# EL_Inverter.net
KiCad netlist of a schematic drawn in EAGLE
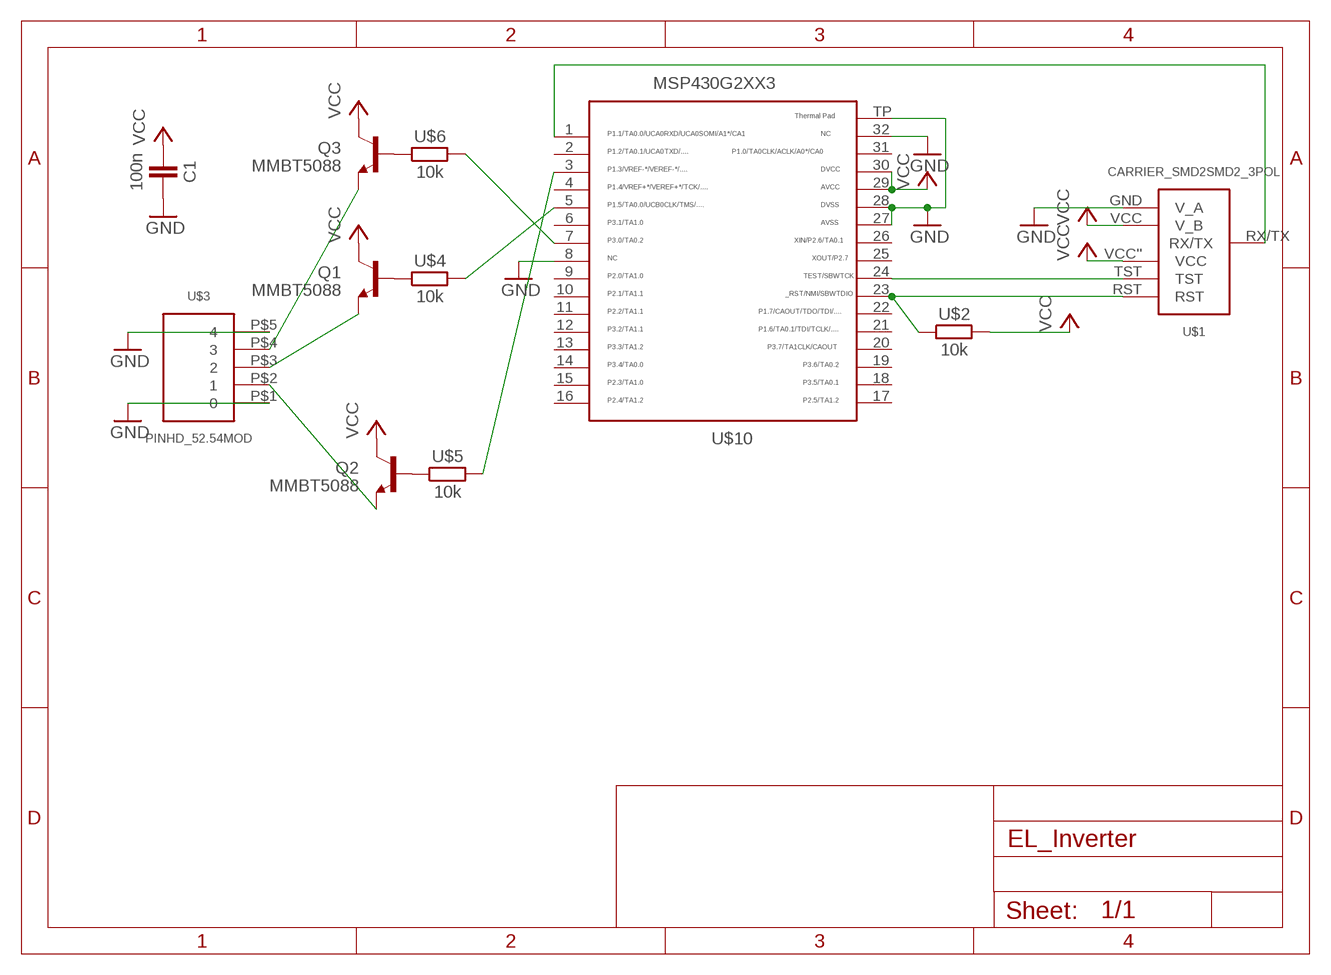
[diagram p0: schematic, sheet 1]

(export (version "E")
  (design (tool "Eeschema 10.0.6"))
  (components
    (comp (ref "C1")
      (value "100n")
      (footprint "eagle-import:603")
      (libsource (lib "eagle-import") (part "CAPACITOR"))
    )
    (comp (ref "Q1")
      (value "MMBT5088")
      (footprint "eagle-import:SOT23-3")
      (libsource (lib "eagle-import") (part "TRANSISTOR_NPNMMBT5088"))
    )
    (comp (ref "Q2")
      (value "MMBT5088")
      (footprint "eagle-import:SOT23-3")
      (libsource (lib "eagle-import") (part "TRANSISTOR_NPNMMBT5088"))
    )
    (comp (ref "Q3")
      (value "MMBT5088")
      (footprint "eagle-import:SOT23-3")
      (libsource (lib "eagle-import") (part "TRANSISTOR_NPNMMBT5088"))
    )
    (comp (ref "U$1")
      (value "CARRIER_SMD2SMD2_3POL")
      (footprint "eagle-import:CARRIER_SMD2_3POL")
      (libsource (lib "eagle-import") (part "CARRIER_SMD2SMD2_3POL"))
    )
    (comp (ref "U$2")
      (value "10k")
      (footprint "eagle-import:603")
      (libsource (lib "eagle-import") (part "RESISTOR0603"))
    )
    (comp (ref "U$3")
      (value "PINHD_52.54MOD")
      (footprint "eagle-import:PINHD_5_MOD")
      (libsource (lib "eagle-import") (part "PINHD_52.54MOD"))
    )
    (comp (ref "U$4")
      (value "10k")
      (footprint "eagle-import:603")
      (libsource (lib "eagle-import") (part "RESISTOR0603"))
    )
    (comp (ref "U$5")
      (value "10k")
      (footprint "eagle-import:603")
      (libsource (lib "eagle-import") (part "RESISTOR0603"))
    )
    (comp (ref "U$6")
      (value "10k")
      (footprint "eagle-import:603")
      (libsource (lib "eagle-import") (part "RESISTOR0603"))
    )
    (comp (ref "U$10")
      (value "MSP430G2553")
      (footprint "eagle-import:QFN32")
      (libsource (lib "eagle-import") (part "MSP430G2553"))
    )
  )
  (nets
    (net (code "1") (name "GND") (class "Default")
      (node (ref "C1") (pin "2") (pinfunction "2_2") (pintype "passive"))
      (node (ref "U$1") (pin "GND") (pinfunction "V_A_GND") (pintype "bidirectional"))
      (node (ref "U$10") (pin "27") (pinfunction "27_27") (pintype "bidirectional"))
      (node (ref "U$10") (pin "28") (pinfunction "28_28") (pintype "bidirectional"))
      (node (ref "U$10") (pin "32") (pinfunction "32_32") (pintype "bidirectional"))
      (node (ref "U$10") (pin "8") (pinfunction "8_8") (pintype "bidirectional"))
      (node (ref "U$10") (pin "TP") (pinfunction "TP_TP") (pintype "bidirectional"))
      (node (ref "U$3") (pin "P$1") (pinfunction "0_P$1") (pintype "bidirectional"))
      (node (ref "U$3") (pin "P$5") (pinfunction "4_P$5") (pintype "bidirectional"))
    )
    (net (code "2") (name "Net-(Q1-B)") (class "Default")
      (node (ref "Q1") (pin "1") (pinfunction "B_1") (pintype "passive"))
      (node (ref "U$4") (pin "1") (pinfunction "1_1") (pintype "passive"))
    )
    (net (code "3") (name "Net-(Q1-E)") (class "Default")
      (node (ref "Q1") (pin "2") (pinfunction "E_2") (pintype "passive"))
      (node (ref "U$3") (pin "P$3") (pinfunction "2_P$3") (pintype "bidirectional"))
    )
    (net (code "4") (name "Net-(Q2-B)") (class "Default")
      (node (ref "Q2") (pin "1") (pinfunction "B_1") (pintype "passive"))
      (node (ref "U$5") (pin "1") (pinfunction "1_1") (pintype "passive"))
    )
    (net (code "5") (name "Net-(Q2-E)") (class "Default")
      (node (ref "Q2") (pin "2") (pinfunction "E_2") (pintype "passive"))
      (node (ref "U$3") (pin "P$2") (pinfunction "1_P$2") (pintype "bidirectional"))
    )
    (net (code "6") (name "Net-(Q3-B)") (class "Default")
      (node (ref "Q3") (pin "1") (pinfunction "B_1") (pintype "passive"))
      (node (ref "U$6") (pin "1") (pinfunction "1_1") (pintype "passive"))
    )
    (net (code "7") (name "Net-(Q3-E)") (class "Default")
      (node (ref "Q3") (pin "2") (pinfunction "E_2") (pintype "passive"))
      (node (ref "U$3") (pin "P$4") (pinfunction "3_P$4") (pintype "bidirectional"))
    )
    (net (code "8") (name "Net-(U$1-PadRST)") (class "Default")
      (node (ref "U$1") (pin "RST") (pinfunction "RST_RST") (pintype "bidirectional"))
      (node (ref "U$10") (pin "23") (pinfunction "23_23") (pintype "bidirectional"))
      (node (ref "U$2") (pin "1") (pinfunction "1_1") (pintype "passive"))
    )
    (net (code "9") (name "Net-(U$1-PadRX{slash}TX)") (class "Default")
      (node (ref "U$1") (pin "RX/TX") (pinfunction "RX/TX_RX/TX") (pintype "bidirectional"))
      (node (ref "U$10") (pin "1") (pinfunction "1_1") (pintype "bidirectional"))
    )
    (net (code "10") (name "Net-(U$1-PadTST)") (class "Default")
      (node (ref "U$1") (pin "TST") (pinfunction "TST_TST") (pintype "bidirectional"))
      (node (ref "U$10") (pin "24") (pinfunction "24_24") (pintype "bidirectional"))
    )
    (net (code "11") (name "Net-(U$10-Pad3)") (class "Default")
      (node (ref "U$10") (pin "3") (pinfunction "3_3") (pintype "bidirectional"))
      (node (ref "U$5") (pin "2") (pinfunction "2_2") (pintype "passive"))
    )
    (net (code "12") (name "Net-(U$10-Pad5)") (class "Default")
      (node (ref "U$10") (pin "5") (pinfunction "5_5") (pintype "bidirectional"))
      (node (ref "U$4") (pin "2") (pinfunction "2_2") (pintype "passive"))
    )
    (net (code "13") (name "Net-(U$10-Pad7)") (class "Default")
      (node (ref "U$10") (pin "7") (pinfunction "7_7") (pintype "bidirectional"))
      (node (ref "U$6") (pin "2") (pinfunction "2_2") (pintype "passive"))
    )
    (net (code "14") (name "VCC") (class "Default")
      (node (ref "C1") (pin "1") (pinfunction "1_1") (pintype "passive"))
      (node (ref "Q1") (pin "3") (pinfunction "C_3") (pintype "passive"))
      (node (ref "Q2") (pin "3") (pinfunction "C_3") (pintype "passive"))
      (node (ref "Q3") (pin "3") (pinfunction "C_3") (pintype "passive"))
      (node (ref "U$1") (pin "VCC") (pinfunction "V_B_VCC") (pintype "bidirectional"))
      (node (ref "U$1") (pin "VCC''") (pinfunction "VCC_VCC''") (pintype "bidirectional"))
      (node (ref "U$10") (pin "29") (pinfunction "29_29") (pintype "bidirectional"))
      (node (ref "U$10") (pin "30") (pinfunction "30_30") (pintype "bidirectional"))
      (node (ref "U$2") (pin "2") (pinfunction "2_2") (pintype "passive"))
    )
    (net (code "15") (name "unconnected-(U$10-Pad2)") (class "Default")
      (node (ref "U$10") (pin "2") (pinfunction "2_2") (pintype "bidirectional"))
    )
    (net (code "16") (name "unconnected-(U$10-Pad4)") (class "Default")
      (node (ref "U$10") (pin "4") (pinfunction "4_4") (pintype "bidirectional"))
    )
    (net (code "17") (name "unconnected-(U$10-Pad6)") (class "Default")
      (node (ref "U$10") (pin "6") (pinfunction "6_6") (pintype "bidirectional"))
    )
    (net (code "18") (name "unconnected-(U$10-Pad9)") (class "Default")
      (node (ref "U$10") (pin "9") (pinfunction "9_9") (pintype "bidirectional"))
    )
    (net (code "19") (name "unconnected-(U$10-Pad10)") (class "Default")
      (node (ref "U$10") (pin "10") (pinfunction "10_10") (pintype "bidirectional"))
    )
    (net (code "20") (name "unconnected-(U$10-Pad11)") (class "Default")
      (node (ref "U$10") (pin "11") (pinfunction "11_11") (pintype "bidirectional"))
    )
    (net (code "21") (name "unconnected-(U$10-Pad12)") (class "Default")
      (node (ref "U$10") (pin "12") (pinfunction "12_12") (pintype "bidirectional"))
    )
    (net (code "22") (name "unconnected-(U$10-Pad13)") (class "Default")
      (node (ref "U$10") (pin "13") (pinfunction "13_13") (pintype "bidirectional"))
    )
    (net (code "23") (name "unconnected-(U$10-Pad14)") (class "Default")
      (node (ref "U$10") (pin "14") (pinfunction "14_14") (pintype "bidirectional"))
    )
    (net (code "24") (name "unconnected-(U$10-Pad15)") (class "Default")
      (node (ref "U$10") (pin "15") (pinfunction "15_15") (pintype "bidirectional"))
    )
    (net (code "25") (name "unconnected-(U$10-Pad16)") (class "Default")
      (node (ref "U$10") (pin "16") (pinfunction "16_16") (pintype "bidirectional"))
    )
    (net (code "26") (name "unconnected-(U$10-Pad17)") (class "Default")
      (node (ref "U$10") (pin "17") (pinfunction "17_17") (pintype "bidirectional"))
    )
    (net (code "27") (name "unconnected-(U$10-Pad18)") (class "Default")
      (node (ref "U$10") (pin "18") (pinfunction "18_18") (pintype "bidirectional"))
    )
    (net (code "28") (name "unconnected-(U$10-Pad19)") (class "Default")
      (node (ref "U$10") (pin "19") (pinfunction "19_19") (pintype "bidirectional"))
    )
    (net (code "29") (name "unconnected-(U$10-Pad20)") (class "Default")
      (node (ref "U$10") (pin "20") (pinfunction "20_20") (pintype "bidirectional"))
    )
    (net (code "30") (name "unconnected-(U$10-Pad21)") (class "Default")
      (node (ref "U$10") (pin "21") (pinfunction "21_21") (pintype "bidirectional"))
    )
    (net (code "31") (name "unconnected-(U$10-Pad22)") (class "Default")
      (node (ref "U$10") (pin "22") (pinfunction "22_22") (pintype "bidirectional"))
    )
    (net (code "32") (name "unconnected-(U$10-Pad25)") (class "Default")
      (node (ref "U$10") (pin "25") (pinfunction "25_25") (pintype "bidirectional"))
    )
    (net (code "33") (name "unconnected-(U$10-Pad26)") (class "Default")
      (node (ref "U$10") (pin "26") (pinfunction "26_26") (pintype "bidirectional"))
    )
    (net (code "34") (name "unconnected-(U$10-Pad31)") (class "Default")
      (node (ref "U$10") (pin "31") (pinfunction "31_31") (pintype "bidirectional"))
    )
  )
)
